# Geiger_v3.net
KiCad netlist of a schematic drawn in EAGLE
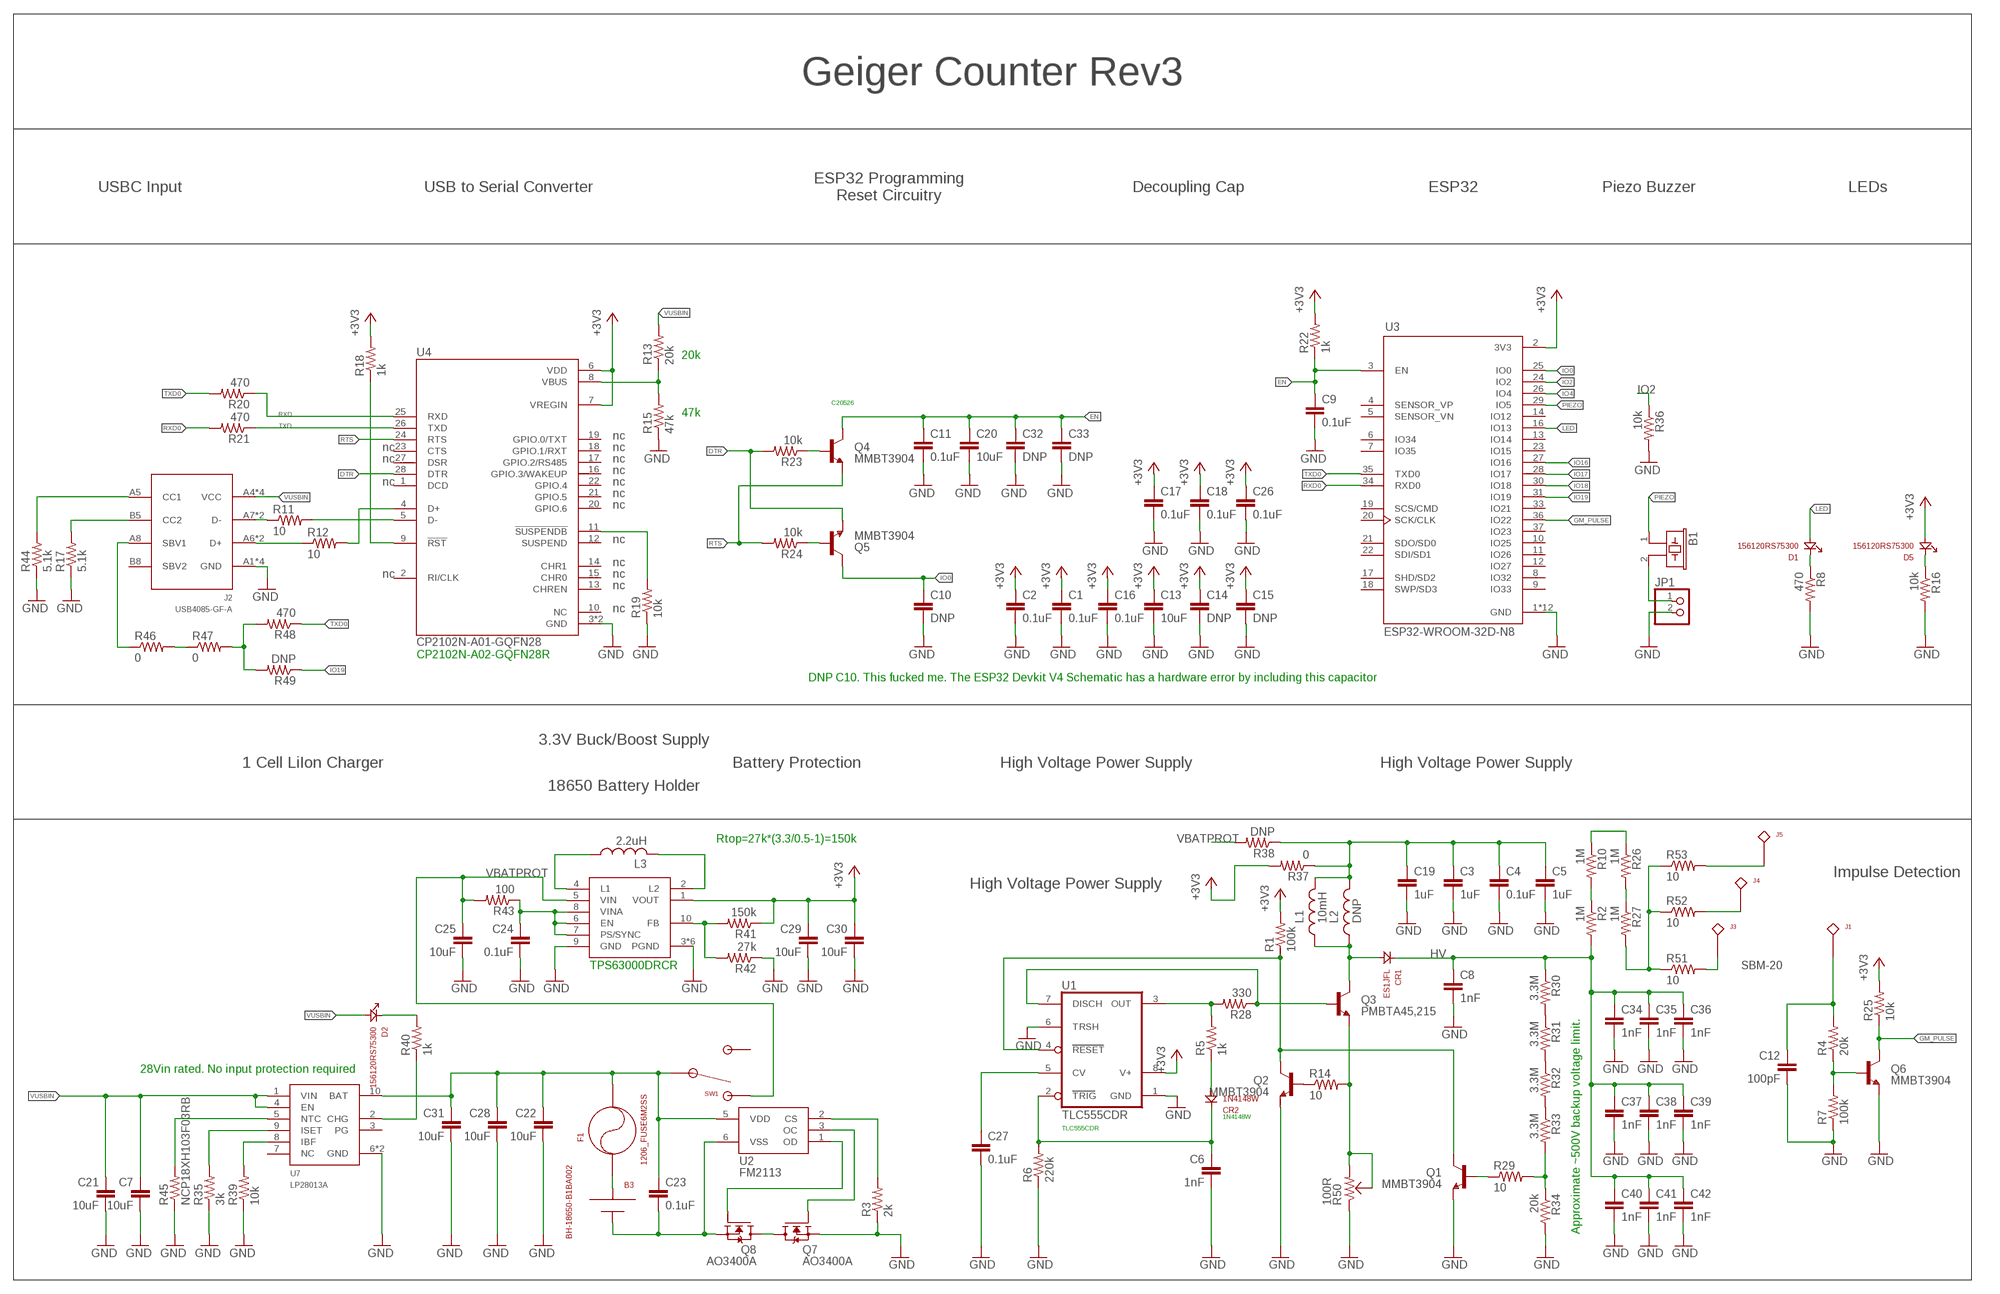
[diagram p0: schematic, sheet 1]

(export (version "E")
  (design (tool "Eeschema 10.0.6"))
  (components
    (comp (ref "B1")
      (value "PIEZO17MM")
      (footprint "eagle-import:PS1740P02E")
      (libsource (lib "eagle-import") (part "PIEZO17MM"))
    )
    (comp (ref "B3")
      (value "BH-18650-B1BA002")
      (footprint "eagle-import:18650")
      (libsource (lib "eagle-import") (part "BH-18650-B1BA002"))
    )
    (comp (ref "C1")
      (value "0.1uF")
      (footprint "eagle-import:0603")
      (libsource (lib "eagle-import") (part "0603_CAPACITOR"))
    )
    (comp (ref "C2")
      (value "0.1uF")
      (footprint "eagle-import:0603")
      (libsource (lib "eagle-import") (part "0603_CAPACITOR"))
    )
    (comp (ref "C3")
      (value "1uF")
      (footprint "eagle-import:0603")
      (libsource (lib "eagle-import") (part "0603_CAPACITOR"))
    )
    (comp (ref "C4")
      (value "0.1uF")
      (footprint "eagle-import:0603")
      (libsource (lib "eagle-import") (part "0603_CAPACITOR"))
    )
    (comp (ref "C5")
      (value "1uF")
      (footprint "eagle-import:0603")
      (libsource (lib "eagle-import") (part "0603_CAPACITOR"))
    )
    (comp (ref "C6")
      (value "1nF")
      (footprint "eagle-import:0603")
      (libsource (lib "eagle-import") (part "0603_CAPACITOR"))
    )
    (comp (ref "C7")
      (value "10uF")
      (footprint "eagle-import:0603")
      (libsource (lib "eagle-import") (part "0603_CAPACITOR"))
    )
    (comp (ref "C8")
      (value "1nF")
      (footprint "eagle-import:1206")
      (libsource (lib "eagle-import") (part "1206_CAPACITOR"))
    )
    (comp (ref "C9")
      (value "0.1uF")
      (footprint "eagle-import:0603")
      (libsource (lib "eagle-import") (part "0603_CAPACITOR"))
    )
    (comp (ref "C10")
      (value "DNP")
      (footprint "eagle-import:0603")
      (libsource (lib "eagle-import") (part "0603_CAPACITOR"))
    )
    (comp (ref "C11")
      (value "0.1uF")
      (footprint "eagle-import:0603")
      (libsource (lib "eagle-import") (part "0603_CAPACITOR"))
    )
    (comp (ref "C12")
      (value "100pF")
      (footprint "eagle-import:0603")
      (libsource (lib "eagle-import") (part "0603_CAPACITOR"))
    )
    (comp (ref "C13")
      (value "10uF")
      (footprint "eagle-import:0603")
      (libsource (lib "eagle-import") (part "0603_CAPACITOR"))
    )
    (comp (ref "C14")
      (value "DNP")
      (footprint "eagle-import:0603")
      (libsource (lib "eagle-import") (part "0603_CAPACITOR"))
    )
    (comp (ref "C15")
      (value "DNP")
      (footprint "eagle-import:0603")
      (libsource (lib "eagle-import") (part "0603_CAPACITOR"))
    )
    (comp (ref "C16")
      (value "0.1uF")
      (footprint "eagle-import:0603")
      (libsource (lib "eagle-import") (part "0603_CAPACITOR"))
    )
    (comp (ref "C17")
      (value "0.1uF")
      (footprint "eagle-import:0603")
      (libsource (lib "eagle-import") (part "0603_CAPACITOR"))
    )
    (comp (ref "C18")
      (value "0.1uF")
      (footprint "eagle-import:0603")
      (libsource (lib "eagle-import") (part "0603_CAPACITOR"))
    )
    (comp (ref "C19")
      (value "1uF")
      (footprint "eagle-import:0603")
      (libsource (lib "eagle-import") (part "0603_CAPACITOR"))
    )
    (comp (ref "C20")
      (value "10uF")
      (footprint "eagle-import:0603")
      (libsource (lib "eagle-import") (part "0603_CAPACITOR"))
    )
    (comp (ref "C21")
      (value "10uF")
      (footprint "eagle-import:0603")
      (libsource (lib "eagle-import") (part "0603_CAPACITOR"))
    )
    (comp (ref "C22")
      (value "10uF")
      (footprint "eagle-import:0603")
      (libsource (lib "eagle-import") (part "0603_CAPACITOR"))
    )
    (comp (ref "C23")
      (value "0.1uF")
      (footprint "eagle-import:0603")
      (libsource (lib "eagle-import") (part "0603_CAPACITOR"))
    )
    (comp (ref "C24")
      (value "0.1uF")
      (footprint "eagle-import:0603")
      (libsource (lib "eagle-import") (part "0603_CAPACITOR"))
    )
    (comp (ref "C25")
      (value "10uF")
      (footprint "eagle-import:0603")
      (libsource (lib "eagle-import") (part "0603_CAPACITOR"))
    )
    (comp (ref "C26")
      (value "0.1uF")
      (footprint "eagle-import:0603")
      (libsource (lib "eagle-import") (part "0603_CAPACITOR"))
    )
    (comp (ref "C27")
      (value "0.1uF")
      (footprint "eagle-import:0603")
      (libsource (lib "eagle-import") (part "0603_CAPACITOR"))
    )
    (comp (ref "C28")
      (value "10uF")
      (footprint "eagle-import:0603")
      (libsource (lib "eagle-import") (part "0603_CAPACITOR"))
    )
    (comp (ref "C29")
      (value "10uF")
      (footprint "eagle-import:0603")
      (libsource (lib "eagle-import") (part "0603_CAPACITOR"))
    )
    (comp (ref "C30")
      (value "10uF")
      (footprint "eagle-import:0603")
      (libsource (lib "eagle-import") (part "0603_CAPACITOR"))
    )
    (comp (ref "C31")
      (value "10uF")
      (footprint "eagle-import:0603")
      (libsource (lib "eagle-import") (part "0603_CAPACITOR"))
    )
    (comp (ref "C32")
      (value "DNP")
      (footprint "eagle-import:0603")
      (libsource (lib "eagle-import") (part "0603_CAPACITOR"))
    )
    (comp (ref "C33")
      (value "DNP")
      (footprint "eagle-import:0603")
      (libsource (lib "eagle-import") (part "0603_CAPACITOR"))
    )
    (comp (ref "C34")
      (value "1nF")
      (footprint "eagle-import:1206")
      (libsource (lib "eagle-import") (part "1206_CAPACITOR"))
    )
    (comp (ref "C35")
      (value "1nF")
      (footprint "eagle-import:1206")
      (libsource (lib "eagle-import") (part "1206_CAPACITOR"))
    )
    (comp (ref "C36")
      (value "1nF")
      (footprint "eagle-import:1206")
      (libsource (lib "eagle-import") (part "1206_CAPACITOR"))
    )
    (comp (ref "C37")
      (value "1nF")
      (footprint "eagle-import:1206")
      (libsource (lib "eagle-import") (part "1206_CAPACITOR"))
    )
    (comp (ref "C38")
      (value "1nF")
      (footprint "eagle-import:1206")
      (libsource (lib "eagle-import") (part "1206_CAPACITOR"))
    )
    (comp (ref "C39")
      (value "1nF")
      (footprint "eagle-import:1206")
      (libsource (lib "eagle-import") (part "1206_CAPACITOR"))
    )
    (comp (ref "C40")
      (value "1nF")
      (footprint "eagle-import:1206")
      (libsource (lib "eagle-import") (part "1206_CAPACITOR"))
    )
    (comp (ref "C41")
      (value "1nF")
      (footprint "eagle-import:1206")
      (libsource (lib "eagle-import") (part "1206_CAPACITOR"))
    )
    (comp (ref "C42")
      (value "1nF")
      (footprint "eagle-import:1206")
      (libsource (lib "eagle-import") (part "1206_CAPACITOR"))
    )
    (comp (ref "CR1")
      (value "ES1JFL")
      (footprint "eagle-import:SOD123(AK)")
      (fields (field (name "PARTNO") "ES1JFLCT-ND"))
      (libsource (lib "eagle-import") (part "ES1JFL"))
    )
    (comp (ref "CR2")
      (value "1N4148W")
      (footprint "eagle-import:SOD123")
      (fields (field (name "PARTNO") "1727-7323-1-ND"))
      (libsource (lib "eagle-import") (part "BAS21GWX"))
    )
    (comp (ref "D1")
      (value "156120RS75300")
      (footprint "eagle-import:1206_REV")
      (fields (field (name "PARTNO") "732-5031-1-ND"))
      (libsource (lib "eagle-import") (part "156120RS75300"))
    )
    (comp (ref "D2")
      (value "156120RS75300")
      (footprint "eagle-import:1206_REV")
      (fields (field (name "PARTNO") "732-5031-1-ND"))
      (libsource (lib "eagle-import") (part "156120RS75300"))
    )
    (comp (ref "D5")
      (value "156120RS75300")
      (footprint "eagle-import:1206_REV")
      (fields (field (name "PARTNO") "732-5031-1-ND"))
      (libsource (lib "eagle-import") (part "156120RS75300"))
    )
    (comp (ref "F1")
      (value "1206_FUSE6M2SS")
      (footprint "eagle-import:1206_FUSE_6M2_SS")
      (libsource (lib "eagle-import") (part "1206_FUSE6M2SS"))
    )
    (comp (ref "J1")
      (value "01010002Z")
      (footprint "eagle-import:01010002Z")
      (fields (field (name "PARTNO") "F4080-ND"))
      (libsource (lib "eagle-import") (part "01010002Z"))
    )
    (comp (ref "J2")
      (value "USB4085-GF-A")
      (footprint "eagle-import:USBC")
      (fields (field (name "PARTNO") "2073-USB4085-GF-ACT-ND"))
      (libsource (lib "eagle-import") (part "USB4085-GF-A"))
    )
    (comp (ref "J3")
      (value "01010002Z")
      (footprint "eagle-import:01010002Z")
      (fields (field (name "PARTNO") "F4080-ND"))
      (libsource (lib "eagle-import") (part "01010002Z"))
    )
    (comp (ref "J4")
      (value "01010002Z")
      (footprint "eagle-import:01010002Z")
      (fields (field (name "PARTNO") "F4080-ND"))
      (libsource (lib "eagle-import") (part "01010002Z"))
    )
    (comp (ref "J5")
      (value "01010002Z")
      (footprint "eagle-import:01010002Z")
      (fields (field (name "PARTNO") "F4080-ND"))
      (libsource (lib "eagle-import") (part "01010002Z"))
    )
    (comp (ref "JP1")
      (value "PINHD-1X2")
      (footprint "eagle-import:1X02")
      (libsource (lib "eagle-import") (part "PINHD-1X2"))
    )
    (comp (ref "L1")
      (value "10mH")
      (footprint "eagle-import:FNR8065S")
      (libsource (lib "eagle-import") (part "FNR8065S103MT"))
    )
    (comp (ref "L2")
      (value "DNP")
      (footprint "eagle-import:SDR1005")
      (fields (field (name "PARTNO") "SDR1005-103KLCT-ND"))
      (libsource (lib "eagle-import") (part "SDR1005-103KL"))
    )
    (comp (ref "L3")
      (value "2.2uH")
      (footprint "eagle-import:CY43")
      (libsource (lib "eagle-import") (part "CY43-2.2UH"))
    )
    (comp (ref "Q1")
      (value "MMBT3904")
      (footprint "eagle-import:SOT23-3_CENTERED")
      (libsource (lib "eagle-import") (part "MMBT3904-TPCENTERED"))
    )
    (comp (ref "Q2")
      (value "MMBT3904")
      (footprint "eagle-import:SOT23-3_CENTERED")
      (libsource (lib "eagle-import") (part "MMBT3904-TPCENTERED"))
    )
    (comp (ref "Q3")
      (value "PMBTA45,215")
      (footprint "eagle-import:SOT23-3")
      (fields (field (name "PARTNO") "1727-5332-1-ND"))
      (libsource (lib "eagle-import") (part "PMBTA45,215"))
    )
    (comp (ref "Q4")
      (value "MMBT3904")
      (footprint "eagle-import:SOT23-3_CENTERED")
      (libsource (lib "eagle-import") (part "MMBT3904-TPCENTERED"))
    )
    (comp (ref "Q5")
      (value "MMBT3904")
      (footprint "eagle-import:SOT23-3_CENTERED")
      (libsource (lib "eagle-import") (part "MMBT3904-TPCENTERED"))
    )
    (comp (ref "Q6")
      (value "MMBT3904")
      (footprint "eagle-import:SOT23-3_CENTERED")
      (libsource (lib "eagle-import") (part "MMBT3904-TPCENTERED"))
    )
    (comp (ref "Q7")
      (value "AO3400A")
      (footprint "eagle-import:SOT23-3_CENTERED")
      (libsource (lib "eagle-import") (part "AO3400A"))
    )
    (comp (ref "Q8")
      (value "AO3400A")
      (footprint "eagle-import:SOT23-3_CENTERED")
      (libsource (lib "eagle-import") (part "AO3400A"))
    )
    (comp (ref "R1")
      (value "100k")
      (footprint "eagle-import:0603")
      (libsource (lib "eagle-import") (part "0603_RESISTOR"))
    )
    (comp (ref "R2")
      (value "1M")
      (footprint "eagle-import:0603")
      (libsource (lib "eagle-import") (part "0603_RESISTOR"))
    )
    (comp (ref "R3")
      (value "2k")
      (footprint "eagle-import:0603")
      (libsource (lib "eagle-import") (part "0603_RESISTOR"))
    )
    (comp (ref "R4")
      (value "20k")
      (footprint "eagle-import:0603")
      (libsource (lib "eagle-import") (part "0603_RESISTOR"))
    )
    (comp (ref "R5")
      (value "1k")
      (footprint "eagle-import:0603")
      (libsource (lib "eagle-import") (part "0603_RESISTOR"))
    )
    (comp (ref "R6")
      (value "220k")
      (footprint "eagle-import:0603")
      (libsource (lib "eagle-import") (part "0603_RESISTOR"))
    )
    (comp (ref "R7")
      (value "100k")
      (footprint "eagle-import:0603")
      (libsource (lib "eagle-import") (part "0603_RESISTOR"))
    )
    (comp (ref "R8")
      (value "470")
      (footprint "eagle-import:0603")
      (libsource (lib "eagle-import") (part "0603_RESISTOR"))
    )
    (comp (ref "R10")
      (value "1M")
      (footprint "eagle-import:0603")
      (libsource (lib "eagle-import") (part "0603_RESISTOR"))
    )
    (comp (ref "R11")
      (value "10")
      (footprint "eagle-import:0603")
      (libsource (lib "eagle-import") (part "0603_RESISTOR"))
    )
    (comp (ref "R12")
      (value "10")
      (footprint "eagle-import:0603")
      (libsource (lib "eagle-import") (part "0603_RESISTOR"))
    )
    (comp (ref "R13")
      (value "20k")
      (footprint "eagle-import:0603")
      (libsource (lib "eagle-import") (part "0603_RESISTOR"))
    )
    (comp (ref "R14")
      (value "10")
      (footprint "eagle-import:0603")
      (libsource (lib "eagle-import") (part "0603_RESISTOR"))
    )
    (comp (ref "R15")
      (value "47k")
      (footprint "eagle-import:0603")
      (libsource (lib "eagle-import") (part "0603_RESISTOR"))
    )
    (comp (ref "R16")
      (value "10k")
      (footprint "eagle-import:0603")
      (libsource (lib "eagle-import") (part "0603_RESISTOR"))
    )
    (comp (ref "R17")
      (value "5.1k")
      (footprint "eagle-import:0603")
      (libsource (lib "eagle-import") (part "0603_RESISTOR"))
    )
    (comp (ref "R18")
      (value "1k")
      (footprint "eagle-import:0603")
      (libsource (lib "eagle-import") (part "0603_RESISTOR"))
    )
    (comp (ref "R19")
      (value "10k")
      (footprint "eagle-import:0603")
      (libsource (lib "eagle-import") (part "0603_RESISTOR"))
    )
    (comp (ref "R20")
      (value "470")
      (footprint "eagle-import:0603")
      (libsource (lib "eagle-import") (part "0603_RESISTOR"))
    )
    (comp (ref "R21")
      (value "470")
      (footprint "eagle-import:0603")
      (libsource (lib "eagle-import") (part "0603_RESISTOR"))
    )
    (comp (ref "R22")
      (value "1k")
      (footprint "eagle-import:0603")
      (libsource (lib "eagle-import") (part "0603_RESISTOR"))
    )
    (comp (ref "R23")
      (value "10k")
      (footprint "eagle-import:0603")
      (libsource (lib "eagle-import") (part "0603_RESISTOR"))
    )
    (comp (ref "R24")
      (value "10k")
      (footprint "eagle-import:0603")
      (libsource (lib "eagle-import") (part "0603_RESISTOR"))
    )
    (comp (ref "R25")
      (value "10k")
      (footprint "eagle-import:0603")
      (libsource (lib "eagle-import") (part "0603_RESISTOR"))
    )
    (comp (ref "R26")
      (value "1M")
      (footprint "eagle-import:0603")
      (libsource (lib "eagle-import") (part "0603_RESISTOR"))
    )
    (comp (ref "R27")
      (value "1M")
      (footprint "eagle-import:0603")
      (libsource (lib "eagle-import") (part "0603_RESISTOR"))
    )
    (comp (ref "R28")
      (value "330")
      (footprint "eagle-import:0603")
      (libsource (lib "eagle-import") (part "0603_RESISTOR"))
    )
    (comp (ref "R29")
      (value "10")
      (footprint "eagle-import:0603")
      (libsource (lib "eagle-import") (part "0603_RESISTOR"))
    )
    (comp (ref "R30")
      (value "3.3M")
      (footprint "eagle-import:0603")
      (libsource (lib "eagle-import") (part "0603_RESISTOR"))
    )
    (comp (ref "R31")
      (value "3.3M")
      (footprint "eagle-import:0603")
      (libsource (lib "eagle-import") (part "0603_RESISTOR"))
    )
    (comp (ref "R32")
      (value "3.3M")
      (footprint "eagle-import:0603")
      (libsource (lib "eagle-import") (part "0603_RESISTOR"))
    )
    (comp (ref "R33")
      (value "3.3M")
      (footprint "eagle-import:0603")
      (libsource (lib "eagle-import") (part "0603_RESISTOR"))
    )
    (comp (ref "R34")
      (value "20k")
      (footprint "eagle-import:0603")
      (libsource (lib "eagle-import") (part "0603_RESISTOR"))
    )
    (comp (ref "R35")
      (value "3k")
      (footprint "eagle-import:0603")
      (libsource (lib "eagle-import") (part "0603_RESISTOR"))
    )
    (comp (ref "R36")
      (value "10k")
      (footprint "eagle-import:0603")
      (libsource (lib "eagle-import") (part "0603_RESISTOR"))
    )
    (comp (ref "R37")
      (value "0")
      (footprint "eagle-import:0603")
      (libsource (lib "eagle-import") (part "0603_RESISTOR"))
    )
    (comp (ref "R38")
      (value "DNP")
      (footprint "eagle-import:0603")
      (libsource (lib "eagle-import") (part "0603_RESISTOR"))
    )
    (comp (ref "R39")
      (value "10k")
      (footprint "eagle-import:0603")
      (libsource (lib "eagle-import") (part "0603_RESISTOR"))
    )
    (comp (ref "R40")
      (value "1k")
      (footprint "eagle-import:0603")
      (libsource (lib "eagle-import") (part "0603_RESISTOR"))
    )
    (comp (ref "R41")
      (value "150k")
      (footprint "eagle-import:0603")
      (libsource (lib "eagle-import") (part "0603_RESISTOR"))
    )
    (comp (ref "R42")
      (value "27k")
      (footprint "eagle-import:0603")
      (libsource (lib "eagle-import") (part "0603_RESISTOR"))
    )
    (comp (ref "R43")
      (value "100")
      (footprint "eagle-import:0603")
      (libsource (lib "eagle-import") (part "0603_RESISTOR"))
    )
    (comp (ref "R44")
      (value "5.1k")
      (footprint "eagle-import:0603")
      (libsource (lib "eagle-import") (part "0603_RESISTOR"))
    )
    (comp (ref "R45")
      (value "NCP18XH103F03RB")
      (footprint "eagle-import:0603")
      (libsource (lib "eagle-import") (part "0603_RESISTOR"))
    )
    (comp (ref "R46")
      (value "0")
      (footprint "eagle-import:1206")
      (libsource (lib "eagle-import") (part "1206_RESISTOR"))
    )
    (comp (ref "R47")
      (value "0")
      (footprint "eagle-import:1206")
      (libsource (lib "eagle-import") (part "1206_RESISTOR"))
    )
    (comp (ref "R48")
      (value "470")
      (footprint "eagle-import:0603")
      (libsource (lib "eagle-import") (part "0603_RESISTOR"))
    )
    (comp (ref "R49")
      (value "DNP")
      (footprint "eagle-import:0603")
      (libsource (lib "eagle-import") (part "0603_RESISTOR"))
    )
    (comp (ref "R50")
      (value "100R")
      (footprint "eagle-import:ST-4")
      (libsource (lib "eagle-import") (part "ST-4ETB101"))
    )
    (comp (ref "R51")
      (value "10")
      (footprint "eagle-import:0603")
      (libsource (lib "eagle-import") (part "0603_RESISTOR"))
    )
    (comp (ref "R52")
      (value "10")
      (footprint "eagle-import:0603")
      (libsource (lib "eagle-import") (part "0603_RESISTOR"))
    )
    (comp (ref "R53")
      (value "10")
      (footprint "eagle-import:0603")
      (libsource (lib "eagle-import") (part "0603_RESISTOR"))
    )
    (comp (ref "SW1")
      (value "SPDT")
      (footprint "eagle-import:TOGGLE_RA")
      (fields (field (name "PARTNO") "EG2362-ND"))
      (libsource (lib "eagle-import") (part "100SP1T2B4M6QE"))
    )
    (comp (ref "U1")
      (value "TLC555CDR")
      (footprint "eagle-import:SOIC8")
      (fields (field (name "PARTNO") "296-52992-ND"))
      (libsource (lib "eagle-import") (part "TLC555CDG4"))
    )
    (comp (ref "U2")
      (value "FM2113")
      (footprint "eagle-import:SOT23-6")
      (libsource (lib "eagle-import") (part "FM2113"))
    )
    (comp (ref "U3")
      (value "ESP32-WROOM-32D-N8")
      (footprint "eagle-import:MODULE_ESP32-WROOM-32D")
      (fields (field (name "MF") "Espressif Systems") (field (name "MP") "ESP32-WROOM-32D"))
      (libsource (lib "eagle-import") (part "ESP32-WROOM-32D"))
    )
    (comp (ref "U4")
      (value "CP2102N-A01-GQFN28")
      (footprint "eagle-import:QFN50P500X500X80-29N")
      (fields (field (name "MF") "Silicon Labs"))
      (libsource (lib "eagle-import") (part "CP2102N-A01-GQFN28"))
    )
    (comp (ref "U6")
      (value "TPS63000DRCR")
      (footprint "eagle-import:S-PVSON-N10")
      (fields (field (name "PARTNO") "296-19641-1-ND"))
      (libsource (lib "eagle-import") (part "TPS63000DRCR"))
    )
    (comp (ref "U7")
      (value "LP28013A")
      (footprint "eagle-import:10DFN")
      (libsource (lib "eagle-import") (part "LP28013A"))
    )
  )
  (nets
    (net (code "1") (name "+3V3") (class "Default")
      (node (ref "C1") (pin "1") (pinfunction "1_1") (pintype "passive"))
      (node (ref "C13") (pin "1") (pinfunction "1_1") (pintype "passive"))
      (node (ref "C14") (pin "1") (pinfunction "1_1") (pintype "passive"))
      (node (ref "C15") (pin "1") (pinfunction "1_1") (pintype "passive"))
      (node (ref "C16") (pin "1") (pinfunction "1_1") (pintype "passive"))
      (node (ref "C17") (pin "1") (pinfunction "1_1") (pintype "passive"))
      (node (ref "C18") (pin "1") (pinfunction "1_1") (pintype "passive"))
      (node (ref "C2") (pin "1") (pinfunction "1_1") (pintype "passive"))
      (node (ref "C26") (pin "1") (pinfunction "1_1") (pintype "passive"))
      (node (ref "C29") (pin "1") (pinfunction "1_1") (pintype "passive"))
      (node (ref "C30") (pin "1") (pinfunction "1_1") (pintype "passive"))
      (node (ref "D5") (pin "A") (pinfunction "A_A") (pintype "bidirectional"))
      (node (ref "R1") (pin "2") (pinfunction "2_2") (pintype "passive"))
      (node (ref "R18") (pin "2") (pinfunction "2_2") (pintype "passive"))
      (node (ref "R22") (pin "2") (pinfunction "2_2") (pintype "passive"))
      (node (ref "R25") (pin "2") (pinfunction "2_2") (pintype "passive"))
      (node (ref "R37") (pin "2") (pinfunction "2_2") (pintype "passive"))
      (node (ref "R41") (pin "1") (pinfunction "1_1") (pintype "passive"))
      (node (ref "U1") (pin "8") (pinfunction "V+_8") (pintype "power_in"))
      (node (ref "U3") (pin "2") (pinfunction "3V3_2") (pintype "power_in"))
      (node (ref "U4") (pin "6") (pinfunction "VDD_6") (pintype "power_in"))
      (node (ref "U4") (pin "7") (pinfunction "VREGIN_7") (pintype "power_in"))
      (node (ref "U6") (pin "1") (pinfunction "VOUT_1") (pintype "bidirectional"))
    )
    (net (code "2") (name "/HV") (class "Default")
      (node (ref "C34") (pin "1") (pinfunction "1_1") (pintype "passive"))
      (node (ref "C35") (pin "1") (pinfunction "1_1") (pintype "passive"))
      (node (ref "C36") (pin "1") (pinfunction "1_1") (pintype "passive"))
      (node (ref "C37") (pin "1") (pinfunction "1_1") (pintype "passive"))
      (node (ref "C38") (pin "1") (pinfunction "1_1") (pintype "passive"))
      (node (ref "C39") (pin "1") (pinfunction "1_1") (pintype "passive"))
      (node (ref "C40") (pin "1") (pinfunction "1_1") (pintype "passive"))
      (node (ref "C41") (pin "1") (pinfunction "1_1") (pintype "passive"))
      (node (ref "C42") (pin "1") (pinfunction "1_1") (pintype "passive"))
      (node (ref "C8") (pin "1") (pinfunction "1_1") (pintype "passive"))
      (node (ref "CR1") (pin "K") (pinfunction "K_K") (pintype "bidirectional"))
      (node (ref "R2") (pin "2") (pinfunction "2_2") (pintype "passive"))
      (node (ref "R30") (pin "1") (pinfunction "1_1") (pintype "passive"))
    )
    (net (code "3") (name "/RXD") (class "Default")
      (node (ref "R20") (pin "1") (pinfunction "1_1") (pintype "passive"))
      (node (ref "U4") (pin "25") (pinfunction "RXD_25") (pintype "input"))
    )
    (net (code "4") (name "/TXD") (class "Default")
      (node (ref "R21") (pin "1") (pinfunction "1_1") (pintype "passive"))
      (node (ref "U4") (pin "26") (pinfunction "TXD_26") (pintype "output"))
    )
    (net (code "5") (name "/VBATPROT") (class "Default")
      (node (ref "C25") (pin "1") (pinfunction "1_1") (pintype "passive"))
      (node (ref "R38") (pin "2") (pinfunction "2_2") (pintype "passive"))
      (node (ref "R43") (pin "2") (pinfunction "2_2") (pintype "passive"))
      (node (ref "SW1") (pin "3") (pinfunction "P$3_3") (pintype "bidirectional"))
      (node (ref "U6") (pin "5") (pinfunction "VIN_5") (pintype "bidirectional"))
    )
    (net (code "6") (name "DTR") (class "Default")
      (node (ref "Q5") (pin "2") (pinfunction "E_2") (pintype "passive"))
      (node (ref "R23") (pin "2") (pinfunction "2_2") (pintype "passive"))
      (node (ref "U4") (pin "28") (pinfunction "DTR_28") (pintype "output"))
    )
    (net (code "7") (name "EN") (class "Default")
      (node (ref "C11") (pin "1") (pinfunction "1_1") (pintype "passive"))
      (node (ref "C20") (pin "1") (pinfunction "1_1") (pintype "passive"))
      (node (ref "C32") (pin "1") (pinfunction "1_1") (pintype "passive"))
      (node (ref "C33") (pin "1") (pinfunction "1_1") (pintype "passive"))
      (node (ref "C9") (pin "1") (pinfunction "1_1") (pintype "passive"))
      (node (ref "Q4") (pin "3") (pinfunction "C_3") (pintype "passive"))
      (node (ref "R22") (pin "1") (pinfunction "1_1") (pintype "passive"))
      (node (ref "U3") (pin "3") (pinfunction "EN_3") (pintype "input"))
    )
    (net (code "8") (name "GM_PULSE") (class "Default")
      (node (ref "Q6") (pin "3") (pinfunction "C_3") (pintype "passive"))
      (node (ref "R25") (pin "1") (pinfunction "1_1") (pintype "passive"))
      (node (ref "U3") (pin "36") (pinfunction "IO22_36") (pintype "bidirectional"))
    )
    (net (code "9") (name "GND") (class "Default")
      (node (ref "C1") (pin "2") (pinfunction "2_2") (pintype "passive"))
      (node (ref "C10") (pin "2") (pinfunction "2_2") (pintype "passive"))
      (node (ref "C11") (pin "2") (pinfunction "2_2") (pintype "passive"))
      (node (ref "C12") (pin "2") (pinfunction "2_2") (pintype "passive"))
      (node (ref "C13") (pin "2") (pinfunction "2_2") (pintype "passive"))
      (node (ref "C14") (pin "2") (pinfunction "2_2") (pintype "passive"))
      (node (ref "C15") (pin "2") (pinfunction "2_2") (pintype "passive"))
      (node (ref "C16") (pin "2") (pinfunction "2_2") (pintype "passive"))
      (node (ref "C17") (pin "2") (pinfunction "2_2") (pintype "passive"))
      (node (ref "C18") (pin "2") (pinfunction "2_2") (pintype "passive"))
      (node (ref "C19") (pin "2") (pinfunction "2_2") (pintype "passive"))
      (node (ref "C2") (pin "2") (pinfunction "2_2") (pintype "passive"))
      (node (ref "C20") (pin "2") (pinfunction "2_2") (pintype "passive"))
      (node (ref "C21") (pin "2") (pinfunction "2_2") (pintype "passive"))
      (node (ref "C22") (pin "2") (pinfunction "2_2") (pintype "passive"))
      (node (ref "C24") (pin "2") (pinfunction "2_2") (pintype "passive"))
      (node (ref "C25") (pin "2") (pinfunction "2_2") (pintype "passive"))
      (node (ref "C26") (pin "2") (pinfunction "2_2") (pintype "passive"))
      (node (ref "C27") (pin "2") (pinfunction "2_2") (pintype "passive"))
      (node (ref "C28") (pin "2") (pinfunction "2_2") (pintype "passive"))
      (node (ref "C29") (pin "2") (pinfunction "2_2") (pintype "passive"))
      (node (ref "C3") (pin "2") (pinfunction "2_2") (pintype "passive"))
      (node (ref "C30") (pin "2") (pinfunction "2_2") (pintype "passive"))
      (node (ref "C31") (pin "2") (pinfunction "2_2") (pintype "passive"))
      (node (ref "C32") (pin "2") (pinfunction "2_2") (pintype "passive"))
      (node (ref "C33") (pin "2") (pinfunction "2_2") (pintype "passive"))
      (node (ref "C34") (pin "2") (pinfunction "2_2") (pintype "passive"))
      (node (ref "C35") (pin "2") (pinfunction "2_2") (pintype "passive"))
      (node (ref "C36") (pin "2") (pinfunction "2_2") (pintype "passive"))
      (node (ref "C37") (pin "2") (pinfunction "2_2") (pintype "passive"))
      (node (ref "C38") (pin "2") (pinfunction "2_2") (pintype "passive"))
      (node (ref "C39") (pin "2") (pinfunction "2_2") (pintype "passive"))
      (node (ref "C4") (pin "2") (pinfunction "2_2") (pintype "passive"))
      (node (ref "C40") (pin "2") (pinfunction "2_2") (pintype "passive"))
      (node (ref "C41") (pin "2") (pinfunction "2_2") (pintype "passive"))
      (node (ref "C42") (pin "2") (pinfunction "2_2") (pintype "passive"))
      (node (ref "C5") (pin "2") (pinfunction "2_2") (pintype "passive"))
      (node (ref "C6") (pin "2") (pinfunction "2_2") (pintype "passive"))
      (node (ref "C7") (pin "2") (pinfunction "2_2") (pintype "passive"))
      (node (ref "C8") (pin "2") (pinfunction "2_2") (pintype "passive"))
      (node (ref "C9") (pin "2") (pinfunction "2_2") (pintype "passive"))
      (node (ref "J2") (pin "A1") (pinfunction "GND_A1") (pintype "bidirectional"))
      (node (ref "J2") (pin "A12") (pinfunction "GND_A12") (pintype "bidirectional"))
      (node (ref "J2") (pin "B1") (pinfunction "GND_B1") (pintype "bidirectional"))
      (node (ref "J2") (pin "B12") (pinfunction "GND_B12") (pintype "bidirectional"))
      (node (ref "JP1") (pin "2") (pinfunction "2_2") (pintype "passive"))
      (node (ref "Q1") (pin "2") (pinfunction "E_2") (pintype "passive"))
      (node (ref "Q2") (pin "2") (pinfunction "E_2") (pintype "passive"))
      (node (ref "Q6") (pin "2") (pinfunction "E_2") (pintype "passive"))
      (node (ref "Q7") (pin "2") (pinfunction "S_2") (pintype "passive"))
      (node (ref "R15") (pin "1") (pinfunction "1_1") (pintype "passive"))
      (node (ref "R16") (pin "2") (pinfunction "2_2") (pintype "passive"))
      (node (ref "R17") (pin "1") (pinfunction "1_1") (pintype "passive"))
      (node (ref "R19") (pin "1") (pinfunction "1_1") (pintype "passive"))
      (node (ref "R3") (pin "1") (pinfunction "1_1") (pintype "passive"))
      (node (ref "R34") (pin "2") (pinfunction "2_2") (pintype "passive"))
      (node (ref "R35") (pin "1") (pinfunction "1_1") (pintype "passive"))
      (node (ref "R36") (pin "2") (pinfunction "2_2") (pintype "passive"))
      (node (ref "R39") (pin "1") (pinfunction "1_1") (pintype "passive"))
      (node (ref "R42") (pin "1") (pinfunction "1_1") (pintype "passive"))
      (node (ref "R44") (pin "1") (pinfunction "1_1") (pintype "passive"))
      (node (ref "R45") (pin "1") (pinfunction "1_1") (pintype "passive"))
      (node (ref "R50") (pin "3") (pinfunction "2_3") (pintype "passive"))
      (node (ref "R6") (pin "1") (pinfunction "1_1") (pintype "passive"))
      (node (ref "R7") (pin "1") (pinfunction "1_1") (pintype "passive"))
      (node (ref "R8") (pin "2") (pinfunction "2_2") (pintype "passive"))
      (node (ref "U1") (pin "1") (pinfunction "GND_1") (pintype "power_in"))
      (node (ref "U1") (pin "6") (pinfunction "TRSH_6") (pintype "input"))
      (node (ref "U3") (pin "1") (pinfunction "GND_1") (pintype "power_in"))
      (node (ref "U3") (pin "15") (pinfunction "GND_15") (pintype "power_in"))
      (node (ref "U3") (pin "38") (pinfunction "GND_38") (pintype "power_in"))
      (node (ref "U3") (pin "39_1") (pinfunction "GND_39_1") (pintype "power_in"))
      (node (ref "U3") (pin "39_2") (pinfunction "GND_39_2") (pintype "power_in"))
      (node (ref "U3") (pin "39_3") (pinfunction "GND_39_3") (pintype "power_in"))
      (node (ref "U3") (pin "39_4") (pinfunction "GND_39_4") (pintype "power_in"))
      (node (ref "U3") (pin "39_5") (pinfunction "GND_39_5") (pintype "power_in"))
      (node (ref "U3") (pin "39_6") (pinfunction "GND_39_6") (pintype "power_in"))
      (node (ref "U3") (pin "39_7") (pinfunction "GND_39_7") (pintype "power_in"))
      (node (ref "U3") (pin "39_8") (pinfunction "GND_39_8") (pintype "power_in"))
      (node (ref "U3") (pin "39_9") (pinfunction "GND_39_9") (pintype "power_in"))
      (node (ref "U4") (pin "29") (pinfunction "GND_29") (pintype "power_in"))
      (node (ref "U4") (pin "3") (pinfunction "GND_3") (pintype "power_in"))
      (node (ref "U6") (pin "3") (pinfunction "PGND_3") (pintype "bidirectional"))
      (node (ref "U6") (pin "9") (pinfunction "GND_9") (pintype "bidirectional"))
      (node (ref "U6") (pin "PG") (pinfunction "PGND_PG") (pintype "bidirectional"))
      (node (ref "U6") (pin "PG1") (pinfunction "PGND_PG1") (pintype "bidirectional"))
      (node (ref "U6") (pin "PG2") (pinfunction "PGND_PG2") (pintype "bidirectional"))
      (node (ref "U6") (pin "PG3") (pinfunction "PGND_PG3") (pintype "bidirectional"))
      (node (ref "U6") (pin "PG4") (pinfunction "PGND_PG4") (pintype "bidirectional"))
      (node (ref "U7") (pin "6") (pinfunction "GND_6") (pintype "bidirectional"))
      (node (ref "U7") (pin "GF") (pinfunction "GND_GF") (pintype "bidirectional"))
    )
    (net (code "10") (name "IO0") (class "Default")
      (node (ref "C10") (pin "1") (pinfunction "1_1") (pintype "passive"))
      (node (ref "Q5") (pin "3") (pinfunction "C_3") (pintype "passive"))
      (node (ref "U3") (pin "25") (pinfunction "IO0_25") (pintype "bidirectional"))
    )
    (net (code "11") (name "IO2") (class "Default")
      (node (ref "R36") (pin "1") (pinfunction "1_1") (pintype "passive"))
      (node (ref "U3") (pin "24") (pinfunction "IO2_24") (pintype "bidirectional"))
    )
    (net (code "12") (name "IO4") (class "Default")
      (node (ref "U3") (pin "26") (pinfunction "IO4_26") (pintype "bidirectional"))
    )
    (net (code "13") (name "IO16") (class "Default")
      (node (ref "U3") (pin "27") (pinfunction "IO16_27") (pintype "bidirectional"))
    )
    (net (code "14") (name "IO17") (class "Default")
      (node (ref "U3") (pin "28") (pinfunction "IO17_28") (pintype "bidirectional"))
    )
    (net (code "15") (name "IO18") (class "Default")
      (node (ref "U3") (pin "30") (pinfunction "IO18_30") (pintype "bidirectional"))
    )
    (net (code "16") (name "IO19") (class "Default")
      (node (ref "R49") (pin "1") (pinfunction "1_1") (pintype "passive"))
      (node (ref "U3") (pin "31") (pinfunction "IO19_31") (pintype "bidirectional"))
    )
    (net (code "17") (name "LED") (class "Default")
      (node (ref "D1") (pin "A") (pinfunction "A_A") (pintype "bidirectional"))
      (node (ref "U3") (pin "16") (pinfunction "IO13_16") (pintype "bidirectional"))
    )
    (net (code "18") (name "Net-(B1-Pad2)") (class "Default")
      (node (ref "B1") (pin "2") (pinfunction "2_2") (pintype "passive"))
      (node (ref "JP1") (pin "1") (pinfunction "1_1") (pintype "passive"))
    )
    (net (code "19") (name "Net-(B3-Pad+)") (class "Default")
      (node (ref "B3") (pin "+") (pinfunction "+_+") (pintype "bidirectional"))
      (node (ref "F1") (pin "P$1") (pinfunction "P$1_P$1") (pintype "bidirectional"))
    )
    (net (code "20") (name "Net-(C12-Pad1)") (class "Default")
      (node (ref "C12") (pin "1") (pinfunction "1_1") (pintype "passive"))
      (node (ref "J1") (pin "P$1") (pinfunction "P$1_P$1") (pintype "bidirectional"))
      (node (ref "R4") (pin "2") (pinfunction "2_2") (pintype "passive"))
    )
    (net (code "21") (name "Net-(C19-Pad1)") (class "Default")
      (node (ref "C19") (pin "1") (pinfunction "1_1") (pintype "passive"))
      (node (ref "C3") (pin "1") (pinfunction "1_1") (pintype "passive"))
      (node (ref "C4") (pin "1") (pinfunction "1_1") (pintype "passive"))
      (node (ref "C5") (pin "1") (pinfunction "1_1") (pintype "passive"))
      (node (ref "L1") (pin "P$2") (pinfunction "P$2_P$2") (pintype "bidirectional"))
      (node (ref "L2") (pin "P$2") (pinfunction "P$2_P$2") (pintype "bidirectional"))
      (node (ref "R37") (pin "1") (pinfunction "1_1") (pintype "passive"))
      (node (ref "R38") (pin "1") (pinfunction "1_1") (pintype "passive"))
    )
    (net (code "22") (name "Net-(CR2-A)") (class "Default")
      (node (ref "CR2") (pin "2") (pinfunction "A_2") (pintype "bidirectional"))
      (node (ref "R5") (pin "1") (pinfunction "1_1") (pintype "passive"))
    )
    (net (code "23") (name "Net-(CR2-K)") (class "Default")
      (node (ref "C6") (pin "1") (pinfunction "1_1") (pintype "passive"))
      (node (ref "CR2") (pin "1") (pinfunction "K_1") (pintype "bidirectional"))
      (node (ref "R6") (pin "2") (pinfunction "2_2") (pintype "passive"))
      (node (ref "U1") (pin "2") (pinfunction "TRIG_2") (pintype "bidirectional"))
    )
    (net (code "24") (name "Net-(D1-PadK)") (class "Default")
      (node (ref "D1") (pin "K") (pinfunction "K_K") (pintype "bidirectional"))
      (node (ref "R8") (pin "1") (pinfunction "1_1") (pintype "passive"))
    )
    (net (code "25") (name "Net-(D2-PadK)") (class "Default")
      (node (ref "D2") (pin "K") (pinfunction "K_K") (pintype "bidirectional"))
      (node (ref "R40") (pin "2") (pinfunction "2_2") (pintype "passive"))
    )
    (net (code "26") (name "Net-(D5-PadK)") (class "Default")
      (node (ref "D5") (pin "K") (pinfunction "K_K") (pintype "bidirectional"))
      (node (ref "R16") (pin "1") (pinfunction "1_1") (pintype "passive"))
    )
    (net (code "27") (name "Net-(J2-CC1)") (class "Default")
      (node (ref "J2") (pin "A5") (pinfunction "CC1_A5") (pintype "bidirectional"))
      (node (ref "R44") (pin "2") (pinfunction "2_2") (pintype "passive"))
    )
    (net (code "28") (name "Net-(J2-CC2)") (class "Default")
      (node (ref "J2") (pin "B5") (pinfunction "CC2_B5") (pintype "bidirectional"))
      (node (ref "R17") (pin "2") (pinfunction "2_2") (pintype "passive"))
    )
    (net (code "29") (name "Net-(J2-D+-PadA6)") (class "Default")
      (node (ref "J2") (pin "A6") (pinfunction "D+_A6") (pintype "bidirectional"))
      (node (ref "J2") (pin "B6") (pinfunction "D+_B6") (pintype "bidirectional"))
      (node (ref "R12") (pin "1") (pinfunction "1_1") (pintype "passive"))
    )
    (net (code "30") (name "Net-(J2-D--PadA7)") (class "Default")
      (node (ref "J2") (pin "A7") (pinfunction "D-_A7") (pintype "bidirectional"))
      (node (ref "J2") (pin "B7") (pinfunction "D-_B7") (pintype "bidirectional"))
      (node (ref "R11") (pin "1") (pinfunction "1_1") (pintype "passive"))
    )
    (net (code "31") (name "Net-(J2-SBV1)") (class "Default")
      (node (ref "J2") (pin "A8") (pinfunction "SBV1_A8") (pintype "bidirectional"))
      (node (ref "R46") (pin "1") (pinfunction "1_1") (pintype "passive"))
    )
    (net (code "32") (name "Net-(J3-PadP$1)") (class "Default")
      (node (ref "J3") (pin "P$1") (pinfunction "P$1_P$1") (pintype "bidirectional"))
      (node (ref "R51") (pin "2") (pinfunction "2_2") (pintype "passive"))
    )
    (net (code "33") (name "Net-(J4-PadP$1)") (class "Default")
      (node (ref "J4") (pin "P$1") (pinfunction "P$1_P$1") (pintype "bidirectional"))
      (node (ref "R52") (pin "2") (pinfunction "2_2") (pintype "passive"))
    )
    (net (code "34") (name "Net-(J5-PadP$1)") (class "Default")
      (node (ref "J5") (pin "P$1") (pinfunction "P$1_P$1") (pintype "bidirectional"))
      (node (ref "R53") (pin "2") (pinfunction "2_2") (pintype "passive"))
    )
    (net (code "35") (name "Net-(L3-1)") (class "Default")
      (node (ref "L3") (pin "P$1") (pinfunction "1_P$1") (pintype "passive"))
      (node (ref "U6") (pin "4") (pinfunction "L1_4") (pintype "bidirectional"))
    )
    (net (code "36") (name "Net-(L3-2)") (class "Default")
      (node (ref "L3") (pin "P$2") (pinfunction "2_P$2") (pintype "passive"))
      (node (ref "U6") (pin "2") (pinfunction "L2_2") (pintype "bidirectional"))
    )
    (net (code "37") (name "Net-(Q1-B)") (class "Default")
      (node (ref "Q1") (pin "1") (pinfunction "B_1") (pintype "passive"))
      (node (ref "R29") (pin "1") (pinfunction "1_1") (pintype "passive"))
    )
    (net (code "38") (name "Net-(Q1-C)") (class "Default")
      (node (ref "Q1") (pin "3") (pinfunction "C_3") (pintype "passive"))
      (node (ref "Q2") (pin "3") (pinfunction "C_3") (pintype "passive"))
      (node (ref "R1") (pin "1") (pinfunction "1_1") (pintype "passive"))
      (node (ref "U1") (pin "4") (pinfunction "RESET_4") (pintype "input"))
    )
    (net (code "39") (name "Net-(Q2-B)") (class "Default")
      (node (ref "Q2") (pin "1") (pinfunction "B_1") (pintype "passive"))
      (node (ref "R14") (pin "1") (pinfunction "1_1") (pintype "passive"))
    )
    (net (code "40") (name "Net-(Q3-B)") (class "Default")
      (node (ref "Q3") (pin "1") (pinfunction "B_1") (pintype "passive"))
      (node (ref "R28") (pin "1") (pinfunction "1_1") (pintype "passive"))
      (node (ref "U1") (pin "7") (pinfunction "DISCH_7") (pintype "input"))
    )
    (net (code "41") (name "Net-(Q3-C)") (class "Default")
      (node (ref "CR1") (pin "A") (pinfunction "A_A") (pintype "bidirectional"))
      (node (ref "L1") (pin "P$1") (pinfunction "P$1_P$1") (pintype "bidirectional"))
      (node (ref "L2") (pin "P$1") (pinfunction "P$1_P$1") (pintype "bidirectional"))
      (node (ref "Q3") (pin "3") (pinfunction "C_3") (pintype "passive"))
    )
    (net (code "42") (name "Net-(Q3-E)") (class "Default")
      (node (ref "Q3") (pin "2") (pinfunction "E_2") (pintype "passive"))
      (node (ref "R14") (pin "2") (pinfunction "2_2") (pintype "passive"))
      (node (ref "R50") (pin "1") (pinfunction "1_1") (pintype "passive"))
      (node (ref "R50") (pin "2") (pinfunction "ADJ_2") (pintype "passive"))
    )
    (net (code "43") (name "Net-(Q4-B)") (class "Default")
      (node (ref "Q4") (pin "1") (pinfunction "B_1") (pintype "passive"))
      (node (ref "R23") (pin "1") (pinfunction "1_1") (pintype "passive"))
    )
    (net (code "44") (name "Net-(Q5-B)") (class "Default")
      (node (ref "Q5") (pin "1") (pinfunction "B_1") (pintype "passive"))
      (node (ref "R24") (pin "1") (pinfunction "1_1") (pintype "passive"))
    )
    (net (code "45") (name "Net-(Q6-B)") (class "Default")
      (node (ref "Q6") (pin "1") (pinfunction "B_1") (pintype "passive"))
      (node (ref "R4") (pin "1") (pinfunction "1_1") (pintype "passive"))
      (node (ref "R7") (pin "2") (pinfunction "2_2") (pintype "passive"))
    )
    (net (code "46") (name "Net-(Q7-D)") (class "Default")
      (node (ref "Q7") (pin "3") (pinfunction "D_3") (pintype "passive"))
      (node (ref "Q8") (pin "3") (pinfunction "D_3") (pintype "passive"))
    )
    (net (code "47") (name "Net-(Q7-G)") (class "Default")
      (node (ref "Q7") (pin "1") (pinfunction "G_1") (pintype "passive"))
      (node (ref "U2") (pin "3") (pinfunction "OC_3") (pintype "bidirectional"))
    )
    (net (code "48") (name "Net-(Q8-G)") (class "Default")
      (node (ref "Q8") (pin "1") (pinfunction "G_1") (pintype "passive"))
      (node (ref "U2") (pin "1") (pinfunction "OD_1") (pintype "bidirectional"))
    )
    (net (code "49") (name "Net-(Q8-S)") (class "Default")
      (node (ref "B3") (pin "-") (pinfunction "-_-") (pintype "bidirectional"))
      (node (ref "C23") (pin "2") (pinfunction "2_2") (pintype "passive"))
      (node (ref "Q8") (pin "2") (pinfunction "S_2") (pintype "passive"))
      (node (ref "U2") (pin "6") (pinfunction "VSS_6") (pintype "bidirectional"))
    )
    (net (code "50") (name "Net-(R10-Pad1)") (class "Default")
      (node (ref "R10") (pin "1") (pinfunction "1_1") (pintype "passive"))
      (node (ref "R26") (pin "1") (pinfunction "1_1") (pintype "passive"))
    )
    (net (code "51") (name "Net-(R10-Pad2)") (class "Default")
      (node (ref "R10") (pin "2") (pinfunction "2_2") (pintype "passive"))
      (node (ref "R2") (pin "1") (pinfunction "1_1") (pintype "passive"))
    )
    (net (code "52") (name "Net-(R26-Pad2)") (class "Default")
      (node (ref "R26") (pin "2") (pinfunction "2_2") (pintype "passive"))
      (node (ref "R27") (pin "1") (pinfunction "1_1") (pintype "passive"))
    )
    (net (code "53") (name "Net-(R27-Pad2)") (class "Default")
      (node (ref "R27") (pin "2") (pinfunction "2_2") (pintype "passive"))
      (node (ref "R51") (pin "1") (pinfunction "1_1") (pintype "passive"))
      (node (ref "R52") (pin "1") (pinfunction "1_1") (pintype "passive"))
      (node (ref "R53") (pin "1") (pinfunction "1_1") (pintype "passive"))
    )
    (net (code "54") (name "Net-(R29-Pad2)") (class "Default")
      (node (ref "R29") (pin "2") (pinfunction "2_2") (pintype "passive"))
      (node (ref "R33") (pin "2") (pinfunction "2_2") (pintype "passive"))
      (node (ref "R34") (pin "1") (pinfunction "1_1") (pintype "passive"))
    )
    (net (code "55") (name "Net-(R30-Pad2)") (class "Default")
      (node (ref "R30") (pin "2") (pinfunction "2_2") (pintype "passive"))
      (node (ref "R31") (pin "1") (pinfunction "1_1") (pintype "passive"))
    )
    (net (code "56") (name "Net-(R31-Pad2)") (class "Default")
      (node (ref "R31") (pin "2") (pinfunction "2_2") (pintype "passive"))
      (node (ref "R32") (pin "1") (pinfunction "1_1") (pintype "passive"))
    )
    (net (code "57") (name "Net-(R32-Pad2)") (class "Default")
      (node (ref "R32") (pin "2") (pinfunction "2_2") (pintype "passive"))
      (node (ref "R33") (pin "1") (pinfunction "1_1") (pintype "passive"))
    )
    (net (code "58") (name "Net-(R46-Pad2)") (class "Default")
      (node (ref "R46") (pin "2") (pinfunction "2_2") (pintype "passive"))
      (node (ref "R47") (pin "1") (pinfunction "1_1") (pintype "passive"))
    )
    (net (code "59") (name "Net-(R47-Pad2)") (class "Default")
      (node (ref "R47") (pin "2") (pinfunction "2_2") (pintype "passive"))
      (node (ref "R48") (pin "2") (pinfunction "2_2") (pintype "passive"))
      (node (ref "R49") (pin "2") (pinfunction "2_2") (pintype "passive"))
    )
    (net (code "60") (name "Net-(SW1-COM)") (class "Default")
      (node (ref "C22") (pin "1") (pinfunction "1_1") (pintype "passive"))
      (node (ref "C23") (pin "1") (pinfunction "1_1") (pintype "passive"))
      (node (ref "C28") (pin "1") (pinfunction "1_1") (pintype "passive"))
      (node (ref "C31") (pin "1") (pinfunction "1_1") (pintype "passive"))
      (node (ref "F1") (pin "P$2") (pinfunction "P$2_P$2") (pintype "bidirectional"))
      (node (ref "SW1") (pin "2") (pinfunction "COM_2") (pintype "bidirectional"))
      (node (ref "U2") (pin "5") (pinfunction "VDD_5") (pintype "bidirectional"))
      (node (ref "U7") (pin "10") (pinfunction "BAT_10") (pintype "bidirectional"))
    )
    (net (code "61") (name "Net-(U1-CV)") (class "Default")
      (node (ref "C27") (pin "1") (pinfunction "1_1") (pintype "passive"))
      (node (ref "U1") (pin "5") (pinfunction "CV_5") (pintype "passive"))
    )
    (net (code "62") (name "Net-(U1-OUT)") (class "Default")
      (node (ref "R28") (pin "2") (pinfunction "2_2") (pintype "passive"))
      (node (ref "R5") (pin "2") (pinfunction "2_2") (pintype "passive"))
      (node (ref "U1") (pin "3") (pinfunction "OUT_3") (pintype "output"))
    )
    (net (code "63") (name "Net-(U2-CS)") (class "Default")
      (node (ref "R3") (pin "2") (pinfunction "2_2") (pintype "passive"))
      (node (ref "U2") (pin "2") (pinfunction "CS_2") (pintype "bidirectional"))
    )
    (net (code "64") (name "Net-(U4-D+)") (class "Default")
      (node (ref "R12") (pin "2") (pinfunction "2_2") (pintype "passive"))
      (node (ref "U4") (pin "4") (pinfunction "D+_4") (pintype "bidirectional"))
    )
    (net (code "65") (name "Net-(U4-D-)") (class "Default")
      (node (ref "R11") (pin "2") (pinfunction "2_2") (pintype "passive"))
      (node (ref "U4") (pin "5") (pinfunction "D-_5") (pintype "bidirectional"))
    )
    (net (code "66") (name "Net-(U4-VBUS)") (class "Default")
      (node (ref "R13") (pin "1") (pinfunction "1_1") (pintype "passive"))
      (node (ref "R15") (pin "2") (pinfunction "2_2") (pintype "passive"))
      (node (ref "U4") (pin "8") (pinfunction "VBUS_8") (pintype "power_in"))
    )
    (net (code "67") (name "Net-(U4-~{RST})") (class "Default")
      (node (ref "R18") (pin "1") (pinfunction "1_1") (pintype "passive"))
      (node (ref "U4") (pin "9") (pinfunction "~{RST}_9") (pintype "input"))
    )
    (net (code "68") (name "Net-(U4-~{SUSPENDB})") (class "Default")
      (node (ref "R19") (pin "2") (pinfunction "2_2") (pintype "passive"))
      (node (ref "U4") (pin "11") (pinfunction "~{SUSPENDB}_11") (pintype "output"))
    )
    (net (code "69") (name "Net-(U6-EN)") (class "Default")
      (node (ref "C24") (pin "1") (pinfunction "1_1") (pintype "passive"))
      (node (ref "R43") (pin "1") (pinfunction "1_1") (pintype "passive"))
      (node (ref "U6") (pin "6") (pinfunction "EN_6") (pintype "bidirectional"))
      (node (ref "U6") (pin "7") (pinfunction "PS/SYNC_7") (pintype "bidirectional"))
      (node (ref "U6") (pin "8") (pinfunction "VINA_8") (pintype "bidirectional"))
    )
    (net (code "70") (name "Net-(U6-FB)") (class "Default")
      (node (ref "R41") (pin "2") (pinfunction "2_2") (pintype "passive"))
      (node (ref "R42") (pin "2") (pinfunction "2_2") (pintype "passive"))
      (node (ref "U6") (pin "10") (pinfunction "FB_10") (pintype "bidirectional"))
    )
    (net (code "71") (name "Net-(U7-CHG)") (class "Default")
      (node (ref "R40") (pin "1") (pinfunction "1_1") (pintype "passive"))
      (node (ref "U7") (pin "2") (pinfunction "CHG_2") (pintype "bidirectional"))
    )
    (net (code "72") (name "Net-(U7-IBF)") (class "Default")
      (node (ref "R39") (pin "2") (pinfunction "2_2") (pintype "passive"))
      (node (ref "U7") (pin "8") (pinfunction "IBF_8") (pintype "bidirectional"))
    )
    (net (code "73") (name "Net-(U7-ISET)") (class "Default")
      (node (ref "R35") (pin "2") (pinfunction "2_2") (pintype "passive"))
      (node (ref "U7") (pin "9") (pinfunction "ISET_9") (pintype "bidirectional"))
    )
    (net (code "74") (name "Net-(U7-NTC)") (class "Default")
      (node (ref "R45") (pin "2") (pinfunction "2_2") (pintype "passive"))
      (node (ref "U7") (pin "5") (pinfunction "NTC_5") (pintype "bidirectional"))
    )
    (net (code "75") (name "PIEZO") (class "Default")
      (node (ref "B1") (pin "1") (pinfunction "1_1") (pintype "passive"))
      (node (ref "U3") (pin "29") (pinfunction "IO5_29") (pintype "bidirectional"))
    )
    (net (code "76") (name "RTS") (class "Default")
      (node (ref "Q4") (pin "2") (pinfunction "E_2") (pintype "passive"))
      (node (ref "R24") (pin "2") (pinfunction "2_2") (pintype "passive"))
      (node (ref "U4") (pin "24") (pinfunction "RTS_24") (pintype "output"))
    )
    (net (code "77") (name "RXD0") (class "Default")
      (node (ref "R21") (pin "2") (pinfunction "2_2") (pintype "passive"))
      (node (ref "U3") (pin "34") (pinfunction "RXD0_34") (pintype "bidirectional"))
    )
    (net (code "78") (name "TXD0") (class "Default")
      (node (ref "R20") (pin "2") (pinfunction "2_2") (pintype "passive"))
      (node (ref "R48") (pin "1") (pinfunction "1_1") (pintype "passive"))
      (node (ref "U3") (pin "35") (pinfunction "TXD0_35") (pintype "bidirectional"))
    )
    (net (code "79") (name "VUSBIN") (class "Default")
      (node (ref "C21") (pin "1") (pinfunction "1_1") (pintype "passive"))
      (node (ref "C7") (pin "1") (pinfunction "1_1") (pintype "passive"))
      (node (ref "D2") (pin "A") (pinfunction "A_A") (pintype "bidirectional"))
      (node (ref "J2") (pin "A4") (pinfunction "VCC_A4") (pintype "bidirectional"))
      (node (ref "J2") (pin "A9") (pinfunction "VCC_A9") (pintype "bidirectional"))
      (node (ref "J2") (pin "B4") (pinfunction "VCC_B4") (pintype "bidirectional"))
      (node (ref "J2") (pin "B9") (pinfunction "VCC_B9") (pintype "bidirectional"))
      (node (ref "R13") (pin "2") (pinfunction "2_2") (pintype "passive"))
      (node (ref "U7") (pin "1") (pinfunction "VIN_1") (pintype "bidirectional"))
      (node (ref "U7") (pin "4") (pinfunction "EN_4") (pintype "bidirectional"))
    )
    (net (code "80") (name "unconnected-(J2-SBV2-PadB8)") (class "Default")
      (node (ref "J2") (pin "B8") (pinfunction "SBV2_B8") (pintype "bidirectional"))
    )
    (net (code "81") (name "unconnected-(SW1-P$2-Pad1)") (class "Default")
      (node (ref "SW1") (pin "1") (pinfunction "P$2_1") (pintype "bidirectional"))
    )
    (net (code "82") (name "unconnected-(U3-IO12-Pad14)") (class "Default")
      (node (ref "U3") (pin "14") (pinfunction "IO12_14") (pintype "bidirectional"))
    )
    (net (code "83") (name "unconnected-(U3-IO14-Pad13)") (class "Default")
      (node (ref "U3") (pin "13") (pinfunction "IO14_13") (pintype "bidirectional"))
    )
    (net (code "84") (name "unconnected-(U3-IO15-Pad23)") (class "Default")
      (node (ref "U3") (pin "23") (pinfunction "IO15_23") (pintype "bidirectional"))
    )
    (net (code "85") (name "unconnected-(U3-IO21-Pad33)") (class "Default")
      (node (ref "U3") (pin "33") (pinfunction "IO21_33") (pintype "bidirectional"))
    )
    (net (code "86") (name "unconnected-(U3-IO23-Pad37)") (class "Default")
      (node (ref "U3") (pin "37") (pinfunction "IO23_37") (pintype "bidirectional"))
    )
    (net (code "87") (name "unconnected-(U3-IO25-Pad10)") (class "Default")
      (node (ref "U3") (pin "10") (pinfunction "IO25_10") (pintype "bidirectional"))
    )
    (net (code "88") (name "unconnected-(U3-IO26-Pad11)") (class "Default")
      (node (ref "U3") (pin "11") (pinfunction "IO26_11") (pintype "bidirectional"))
    )
    (net (code "89") (name "unconnected-(U3-IO27-Pad12)") (class "Default")
      (node (ref "U3") (pin "12") (pinfunction "IO27_12") (pintype "bidirectional"))
    )
    (net (code "90") (name "unconnected-(U3-IO32-Pad8)") (class "Default")
      (node (ref "U3") (pin "8") (pinfunction "IO32_8") (pintype "bidirectional"))
    )
    (net (code "91") (name "unconnected-(U3-IO33-Pad9)") (class "Default")
      (node (ref "U3") (pin "9") (pinfunction "IO33_9") (pintype "bidirectional"))
    )
    (net (code "92") (name "unconnected-(U3-IO34-Pad6)") (class "Default")
      (node (ref "U3") (pin "6") (pinfunction "IO34_6") (pintype "input"))
    )
    (net (code "93") (name "unconnected-(U3-IO35-Pad7)") (class "Default")
      (node (ref "U3") (pin "7") (pinfunction "IO35_7") (pintype "input"))
    )
    (net (code "94") (name "unconnected-(U3-SCK{slash}CLK-Pad20)") (class "Default")
      (node (ref "U3") (pin "20") (pinfunction "SCK/CLK_20") (pintype "bidirectional"))
    )
    (net (code "95") (name "unconnected-(U3-SCS{slash}CMD-Pad19)") (class "Default")
      (node (ref "U3") (pin "19") (pinfunction "SCS/CMD_19") (pintype "bidirectional"))
    )
    (net (code "96") (name "unconnected-(U3-SDI{slash}SD1-Pad22)") (class "Default")
      (node (ref "U3") (pin "22") (pinfunction "SDI/SD1_22") (pintype "bidirectional"))
    )
    (net (code "97") (name "unconnected-(U3-SDO{slash}SD0-Pad21)") (class "Default")
      (node (ref "U3") (pin "21") (pinfunction "SDO/SD0_21") (pintype "bidirectional"))
    )
    (net (code "98") (name "unconnected-(U3-SENSOR_VN-Pad5)") (class "Default")
      (node (ref "U3") (pin "5") (pinfunction "SENSOR_VN_5") (pintype "input"))
    )
    (net (code "99") (name "unconnected-(U3-SENSOR_VP-Pad4)") (class "Default")
      (node (ref "U3") (pin "4") (pinfunction "SENSOR_VP_4") (pintype "input"))
    )
    (net (code "100") (name "unconnected-(U3-SHD{slash}SD2-Pad17)") (class "Default")
      (node (ref "U3") (pin "17") (pinfunction "SHD/SD2_17") (pintype "bidirectional"))
    )
    (net (code "101") (name "unconnected-(U3-SWP{slash}SD3-Pad18)") (class "Default")
      (node (ref "U3") (pin "18") (pinfunction "SWP/SD3_18") (pintype "bidirectional"))
    )
    (net (code "102") (name "unconnected-(U4-CHR0-Pad15)") (class "Default")
      (node (ref "U4") (pin "15") (pinfunction "CHR0_15") (pintype "output"))
    )
    (net (code "103") (name "unconnected-(U4-CHR1-Pad14)") (class "Default")
      (node (ref "U4") (pin "14") (pinfunction "CHR1_14") (pintype "output"))
    )
    (net (code "104") (name "unconnected-(U4-CHREN-Pad13)") (class "Default")
      (node (ref "U4") (pin "13") (pinfunction "CHREN_13") (pintype "output"))
    )
    (net (code "105") (name "unconnected-(U4-CTS-Pad23)") (class "Default")
      (node (ref "U4") (pin "23") (pinfunction "CTS_23") (pintype "input"))
    )
    (net (code "106") (name "unconnected-(U4-DCD-Pad1)") (class "Default")
      (node (ref "U4") (pin "1") (pinfunction "DCD_1") (pintype "input"))
    )
    (net (code "107") (name "unconnected-(U4-DSR-Pad27)") (class "Default")
      (node (ref "U4") (pin "27") (pinfunction "DSR_27") (pintype "input"))
    )
    (net (code "108") (name "unconnected-(U4-GPIO.0{slash}TXT-Pad19)") (class "Default")
      (node (ref "U4") (pin "19") (pinfunction "GPIO.0/TXT_19") (pintype "bidirectional"))
    )
    (net (code "109") (name "unconnected-(U4-GPIO.1{slash}RXT-Pad18)") (class "Default")
      (node (ref "U4") (pin "18") (pinfunction "GPIO.1/RXT_18") (pintype "bidirectional"))
    )
    (net (code "110") (name "unconnected-(U4-GPIO.2{slash}RS485-Pad17)") (class "Default")
      (node (ref "U4") (pin "17") (pinfunction "GPIO.2/RS485_17") (pintype "bidirectional"))
    )
    (net (code "111") (name "unconnected-(U4-GPIO.3{slash}WAKEUP-Pad16)") (class "Default")
      (node (ref "U4") (pin "16") (pinfunction "GPIO.3/WAKEUP_16") (pintype "bidirectional"))
    )
    (net (code "112") (name "unconnected-(U4-GPIO.4-Pad22)") (class "Default")
      (node (ref "U4") (pin "22") (pinfunction "GPIO.4_22") (pintype "bidirectional"))
    )
    (net (code "113") (name "unconnected-(U4-GPIO.5-Pad21)") (class "Default")
      (node (ref "U4") (pin "21") (pinfunction "GPIO.5_21") (pintype "bidirectional"))
    )
    (net (code "114") (name "unconnected-(U4-GPIO.6-Pad20)") (class "Default")
      (node (ref "U4") (pin "20") (pinfunction "GPIO.6_20") (pintype "bidirectional"))
    )
    (net (code "115") (name "unconnected-(U4-NC-Pad10)") (class "Default")
      (node (ref "U4") (pin "10") (pinfunction "NC_10") (pintype "no_connect"))
    )
    (net (code "116") (name "unconnected-(U4-RI{slash}CLK-Pad2)") (class "Default")
      (node (ref "U4") (pin "2") (pinfunction "RI/CLK_2") (pintype "bidirectional"))
    )
    (net (code "117") (name "unconnected-(U4-SUSPEND-Pad12)") (class "Default")
      (node (ref "U4") (pin "12") (pinfunction "SUSPEND_12") (pintype "output"))
    )
    (net (code "118") (name "unconnected-(U7-NC-Pad7)") (class "Default")
      (node (ref "U7") (pin "7") (pinfunction "NC_7") (pintype "bidirectional"))
    )
    (net (code "119") (name "unconnected-(U7-PG-Pad3)") (class "Default")
      (node (ref "U7") (pin "3") (pinfunction "PG_3") (pintype "bidirectional"))
    )
  )
)
